# Joakims_fulle_kort_kretsskjema.net
KiCad netlist of a schematic drawn in EasyEDA
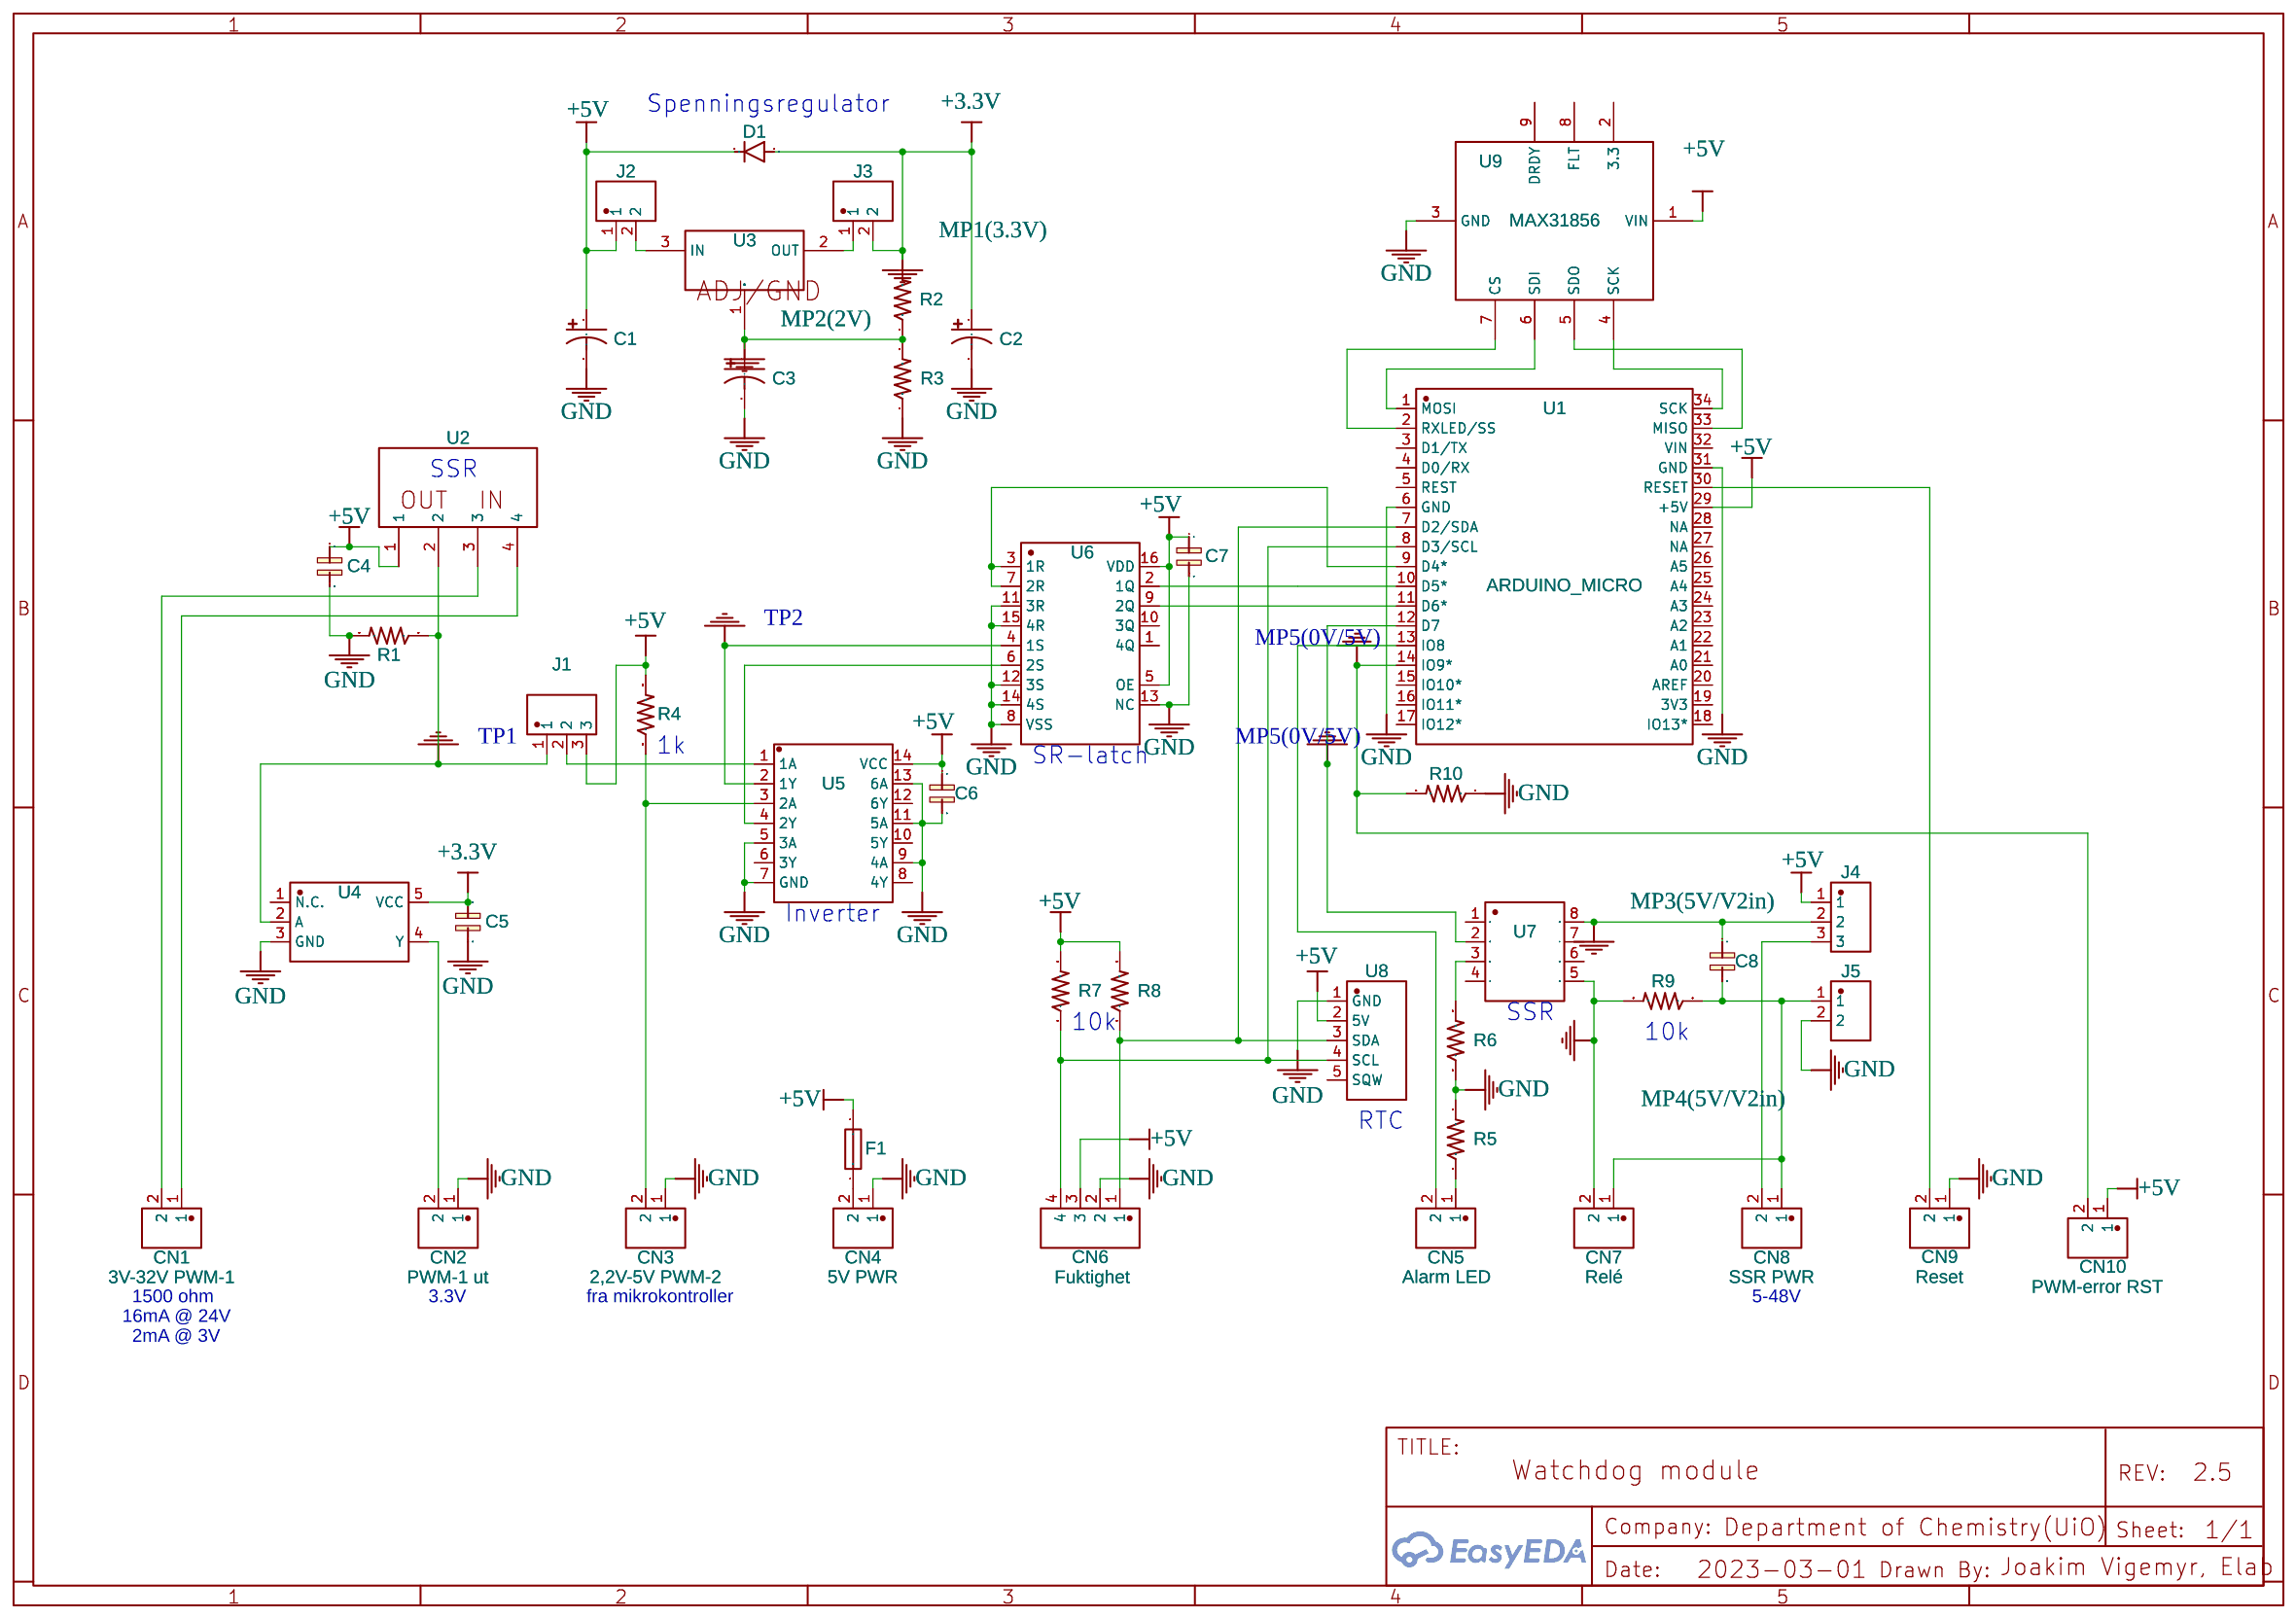
[diagram p0: schematic sheet]

(export (version "E")
  (design (tool "Eeschema 10.0.6"))
  (components
    (comp (ref "C1") (value "10uF") (libsource (lib "") (part "CAP_POLPTH1")))
    (comp (ref "C2") (value "100uF") (libsource (lib "") (part "CAP_POLPTH1")))
    (comp (ref "C3") (value "47uF") (libsource (lib "") (part "CAP_POLPTH1_1")))
    (comp (ref "C4")
      (value "C_3216MP")
      (fields (field (name "BOM_Manufacturer Part") "?"))
      (libsource (lib "") (part "Unknown_-60_-570"))
    )
    (comp (ref "C5")
      (value "C_3216MP")
      (fields (field (name "BOM_Manufacturer Part") "?"))
      (libsource (lib "") (part "Unknown_10_-390"))
    )
    (comp (ref "C6")
      (value "C_3216MP")
      (fields (field (name "BOM_Manufacturer Part") "?"))
      (libsource (lib "") (part "Unknown_250_-455"))
    )
    (comp (ref "C7")
      (value "C_3216MP")
      (fields (field (name "BOM_Manufacturer Part") "?"))
      (libsource (lib "") (part "Unknown_375_-575"))
    )
    (comp (ref "C8")
      (value "C_3216MP")
      (fields (field (name "BOM_Manufacturer Part") "?"))
      (libsource (lib "") (part "Unknown_645_-370"))
    )
    (comp (ref "CN1")
      (value "3V-32V PWM-1")
      (fields (field (name "BOM_Manufacturer Part") "1754436") (field (name "BOM_Supplier Part") "C3586499"))
      (libsource (lib "") (part "1754436"))
    )
    (comp (ref "CN2")
      (value "PWM-1 ut")
      (fields (field (name "BOM_Manufacturer Part") "1754436") (field (name "BOM_Supplier Part") "C3586499"))
      (libsource (lib "") (part "1754436"))
    )
    (comp (ref "CN3")
      (value "2,2V-5V PWM-2")
      (fields (field (name "BOM_Manufacturer Part") "1754436") (field (name "BOM_Supplier Part") "C3586499"))
      (libsource (lib "") (part "1754436"))
    )
    (comp (ref "CN4")
      (value "5V PWR")
      (fields (field (name "BOM_Manufacturer Part") "1754436") (field (name "BOM_Supplier Part") "C3586499"))
      (libsource (lib "") (part "1754436"))
    )
    (comp (ref "CN5")
      (value "Alarm LED")
      (fields (field (name "BOM_Manufacturer Part") "1754436") (field (name "BOM_Supplier Part") "C3586499"))
      (libsource (lib "") (part "1754436"))
    )
    (comp (ref "CN6")
      (value "Fuktighet")
      (fields (field (name "BOM_Manufacturer Part") "1888700") (field (name "BOM_Supplier Part") "C3816378"))
      (libsource (lib "") (part "1888700"))
    )
    (comp (ref "CN7")
      (value "Relé")
      (fields (field (name "BOM_Manufacturer Part") "1754436") (field (name "BOM_Supplier Part") "C3586499"))
      (libsource (lib "") (part "1754436"))
    )
    (comp (ref "CN8")
      (value "SSR PWR")
      (fields (field (name "BOM_Manufacturer Part") "1754436") (field (name "BOM_Supplier Part") "C3586499"))
      (libsource (lib "") (part "1754436"))
    )
    (comp (ref "CN9")
      (value "Reset")
      (fields (field (name "BOM_Manufacturer Part") "1754436") (field (name "BOM_Supplier Part") "C3586499"))
      (libsource (lib "") (part "1754436"))
    )
    (comp (ref "CN10")
      (value "PWM-error RST")
      (fields (field (name "BOM_Manufacturer Part") "1754436") (field (name "BOM_Supplier Part") "C3586499"))
      (libsource (lib "") (part "1754436"))
    )
    (comp (ref "D1") (value "1N4007") (libsource (lib "") (part "DIODEKIT2")))
    (comp (ref "F1")
      (value "0326025.MXP")
      (fields (field (name "BOM_Supplier Part") "C178977"))
      (libsource (lib "") (part "0326025.MXP"))
    )
    (comp (ref "J1")
      (value "JUMPER3")
      (fields (field (name "BOM_Manufacturer Part") "Jumper3") (field (name "BOM_Supplier Part") "C2940050"))
      (libsource (lib "") (part "JUMPER3"))
    )
    (comp (ref "J2")
      (value "JUMPER2")
      (fields (field (name "BOM_Manufacturer Part") "Jumper2") (field (name "BOM_Supplier Part") "C2940092"))
      (libsource (lib "") (part "JUMPER2_1"))
    )
    (comp (ref "J3")
      (value "JUMPER2")
      (fields (field (name "BOM_Manufacturer Part") "Jumper2") (field (name "BOM_Supplier Part") "C2940092"))
      (libsource (lib "") (part "JUMPER2_1"))
    )
    (comp (ref "J4")
      (value "JUMPER3")
      (fields (field (name "BOM_Manufacturer Part") "Jumper3") (field (name "BOM_Supplier Part") "C2940050"))
      (libsource (lib "") (part "JUMPER3_1"))
    )
    (comp (ref "J5")
      (value "JUMPER2")
      (fields (field (name "BOM_Manufacturer Part") "Jumper2") (field (name "BOM_Supplier Part") "C2940092"))
      (libsource (lib "") (part "JUMPER2"))
    )
    (comp (ref "R1") (value "200ohm") (libsource (lib "") (part "RESISTORPTH-14W-VERT_1")))
    (comp (ref "R2") (value "200ohm") (libsource (lib "") (part "RESISTORPTH-14W-VERT")))
    (comp (ref "R3") (value "330ohm") (libsource (lib "") (part "RESISTORPTH-14W-VERT")))
    (comp (ref "R4") (value "1k") (libsource (lib "") (part "RESISTORPTH-14W-VERT")))
    (comp (ref "R5") (value "180ohm") (libsource (lib "") (part "RESISTORPTH-14W-VERT")))
    (comp (ref "R6") (value "330ohm") (libsource (lib "") (part "RESISTORPTH-14W-VERT")))
    (comp (ref "R7") (value "10k") (libsource (lib "") (part "RESISTORPTH-14W-VERT")))
    (comp (ref "R8") (value "10k") (libsource (lib "") (part "RESISTORPTH-14W-VERT")))
    (comp (ref "R9") (value "10k") (libsource (lib "") (part "RESISTORPTH-14W-VERT_1")))
    (comp (ref "R10") (value "10k") (libsource (lib "") (part "RESISTORPTH-14W-VERT_1")))
    (comp (ref "U1") (value "ARDUINO_MICRO") (libsource (lib "") (part "ARDUINO_MICRO")))
    (comp (ref "U2")
      (value "MPDCD3")
      (fields (field (name "BOM_Manufacturer Part") "MPDCD3-B") (field (name "BOM_Supplier Part") "C2616825"))
      (libsource (lib "") (part "MPDCD3-B"))
    )
    (comp (ref "U3")
      (value "TLV1117")
      (fields
        (field (name "BOM_Manufacturer Part") "TLV1117-18CKVURG3")
        (field (name "BOM_Supplier Part") "C2870812")
      )
      (libsource (lib "") (part "TLV1117-18CKVURG3"))
    )
    (comp (ref "U4")
      (value "SN74LVC1G34")
      (fields
        (field (name "BOM_Manufacturer Part") "SN74LVC1G17DBVT")
        (field (name "BOM_Supplier Part") "C2862344")
      )
      (libsource (lib "") (part "SN74LVC1G17DBVT"))
    )
    (comp (ref "U5")
      (value "SN74ACT04D")
      (fields
        (field (name "BOM_Manufacturer Part") "SN74AC04DR")
        (field (name "BOM_Supplier Part") "C352940")
      )
      (libsource (lib "") (part "SN74AC04DR"))
    )
    (comp (ref "U6")
      (value "HEF4043BT,652")
      (fields
        (field (name "BOM_Manufacturer Part") "HEF4543BT,653")
        (field (name "BOM_Supplier Part") "C131489")
      )
      (libsource (lib "") (part "Unknown_320_-570"))
    )
    (comp (ref "U7")
      (value "XR2A-0811-N")
      (fields (field (name "BOM_Supplier Part") "C231487"))
      (libsource (lib "") (part "XR2A-0811-N"))
    )
    (comp (ref "U8") (value "DS1307") (libsource (lib "") (part "DS1307")))
    (comp (ref "U9") (value "MAX31856") (libsource (lib "") (part "Unknown_560_-735")))
  )
  (nets
    (net (code "1") (name "+3.3V") (class "Default")
      (node (ref "C2") (pin "1") (pinfunction "+_1") (pintype "unspecified"))
      (node (ref "C5") (pin "1") (pinfunction "1_1") (pintype "bidirectional"))
      (node (ref "D1") (pin "A") (pinfunction "A_A") (pintype "unspecified"))
      (node (ref "J3") (pin "2") (pinfunction "2_2") (pintype "unspecified"))
      (node (ref "R2") (pin "P$2") (pinfunction "2_P$2") (pintype "unspecified"))
      (node (ref "U4") (pin "5") (pinfunction "VCC_5") (pintype "unspecified"))
    )
    (net (code "2") (name "+5V") (class "Default")
      (node (ref "C1") (pin "1") (pinfunction "+_1") (pintype "unspecified"))
      (node (ref "C4") (pin "1") (pinfunction "1_1") (pintype "bidirectional"))
      (node (ref "C6") (pin "1") (pinfunction "1_1") (pintype "bidirectional"))
      (node (ref "C7") (pin "1") (pinfunction "1_1") (pintype "bidirectional"))
      (node (ref "CN10") (pin "1") (pinfunction "1_1") (pintype "unspecified"))
      (node (ref "CN6") (pin "3") (pinfunction "3_3") (pintype "unspecified"))
      (node (ref "D1") (pin "C") (pinfunction "C_C") (pintype "unspecified"))
      (node (ref "F1") (pin "2") (pinfunction "2_2") (pintype "unspecified"))
      (node (ref "J1") (pin "3") (pinfunction "3_3") (pintype "unspecified"))
      (node (ref "J2") (pin "1") (pinfunction "1_1") (pintype "unspecified"))
      (node (ref "J4") (pin "1") (pinfunction "1_1") (pintype "unspecified"))
      (node (ref "R4") (pin "P$2") (pinfunction "2_P$2") (pintype "unspecified"))
      (node (ref "R7") (pin "P$2") (pinfunction "2_P$2") (pintype "unspecified"))
      (node (ref "R8") (pin "P$2") (pinfunction "2_P$2") (pintype "unspecified"))
      (node (ref "U1") (pin "29") (pinfunction "+5V_29") (pintype "unspecified"))
      (node (ref "U2") (pin "1") (pinfunction "1_1") (pintype "unspecified"))
      (node (ref "U5") (pin "14") (pinfunction "VCC_14") (pintype "unspecified"))
      (node (ref "U6") (pin "16") (pinfunction "VDD_16") (pintype "unspecified"))
      (node (ref "U6") (pin "5") (pinfunction "OE_5") (pintype "unspecified"))
      (node (ref "U8") (pin "2") (pinfunction "5V_2") (pintype "unspecified"))
      (node (ref "U9") (pin "1") (pinfunction "VIN_1") (pintype "unspecified"))
    )
    (net (code "3") (name "GND") (class "Default")
      (node (ref "C1") (pin "2") (pinfunction "-_2") (pintype "unspecified"))
      (node (ref "C2") (pin "2") (pinfunction "-_2") (pintype "unspecified"))
      (node (ref "C3") (pin "2") (pinfunction "-_2") (pintype "unspecified"))
      (node (ref "C4") (pin "2") (pinfunction "2_2") (pintype "bidirectional"))
      (node (ref "C5") (pin "2") (pinfunction "2_2") (pintype "bidirectional"))
      (node (ref "C6") (pin "2") (pinfunction "2_2") (pintype "bidirectional"))
      (node (ref "C7") (pin "2") (pinfunction "2_2") (pintype "bidirectional"))
      (node (ref "CN2") (pin "1") (pinfunction "1_1") (pintype "unspecified"))
      (node (ref "CN3") (pin "1") (pinfunction "1_1") (pintype "unspecified"))
      (node (ref "CN4") (pin "1") (pinfunction "1_1") (pintype "unspecified"))
      (node (ref "CN6") (pin "2") (pinfunction "2_2") (pintype "unspecified"))
      (node (ref "CN9") (pin "1") (pinfunction "1_1") (pintype "unspecified"))
      (node (ref "J5") (pin "2") (pinfunction "2_2") (pintype "unspecified"))
      (node (ref "R1") (pin "P$2") (pinfunction "2_P$2") (pintype "unspecified"))
      (node (ref "R10") (pin "P$1") (pinfunction "1_P$1") (pintype "unspecified"))
      (node (ref "R3") (pin "P$1") (pinfunction "1_P$1") (pintype "unspecified"))
      (node (ref "R5") (pin "P$2") (pinfunction "2_P$2") (pintype "unspecified"))
      (node (ref "R6") (pin "P$1") (pinfunction "1_P$1") (pintype "unspecified"))
      (node (ref "U1") (pin "31") (pinfunction "GND_31") (pintype "unspecified"))
      (node (ref "U1") (pin "6") (pinfunction "GND_6") (pintype "unspecified"))
      (node (ref "U4") (pin "3") (pinfunction "GND_3") (pintype "unspecified"))
      (node (ref "U5") (pin "11") (pinfunction "5A_11") (pintype "unspecified"))
      (node (ref "U5") (pin "13") (pinfunction "6A_13") (pintype "unspecified"))
      (node (ref "U5") (pin "5") (pinfunction "3A_5") (pintype "unspecified"))
      (node (ref "U5") (pin "7") (pinfunction "GND_7") (pintype "unspecified"))
      (node (ref "U5") (pin "9") (pinfunction "4A_9") (pintype "unspecified"))
      (node (ref "U6") (pin "11") (pinfunction "3R_11") (pintype "unspecified"))
      (node (ref "U6") (pin "12") (pinfunction "3S_12") (pintype "unspecified"))
      (node (ref "U6") (pin "13") (pinfunction "NC_13") (pintype "unspecified"))
      (node (ref "U6") (pin "14") (pinfunction "4S_14") (pintype "unspecified"))
      (node (ref "U6") (pin "15") (pinfunction "4R_15") (pintype "unspecified"))
      (node (ref "U6") (pin "8") (pinfunction "VSS_8") (pintype "unspecified"))
      (node (ref "U8") (pin "1") (pinfunction "GND_1") (pintype "unspecified"))
      (node (ref "U9") (pin "3") (pinfunction "GND_3") (pintype "unspecified"))
    )
    (net (code "4") (name "MP2(2V)") (class "Default")
      (node (ref "C3") (pin "1") (pinfunction "+_1") (pintype "unspecified"))
      (node (ref "R2") (pin "P$1") (pinfunction "1_P$1") (pintype "unspecified"))
      (node (ref "R3") (pin "P$2") (pinfunction "2_P$2") (pintype "unspecified"))
      (node (ref "U3") (pin "1") (pinfunction "ADJ/GND_1") (pintype "passive"))
    )
    (net (code "5") (name "MP3(5V{slash}V2in)") (class "Default")
      (node (ref "C8") (pin "1") (pinfunction "1_1") (pintype "bidirectional"))
      (node (ref "J4") (pin "2") (pinfunction "2_2") (pintype "unspecified"))
      (node (ref "U7") (pin "8") (pinfunction "8_8") (pintype "unspecified"))
    )
    (net (code "6") (name "MP4(5V{slash}V2in)") (class "Default")
      (node (ref "CN7") (pin "2") (pinfunction "2_2") (pintype "unspecified"))
      (node (ref "R9") (pin "P$2") (pinfunction "2_P$2") (pintype "unspecified"))
      (node (ref "U7") (pin "5") (pinfunction "5_5") (pintype "unspecified"))
    )
    (net (code "7") (name "MP5(0V{slash}5V)") (class "Default")
      (node (ref "CN10") (pin "2") (pinfunction "2_2") (pintype "unspecified"))
      (node (ref "R10") (pin "P$2") (pinfunction "2_P$2") (pintype "unspecified"))
      (node (ref "U1") (pin "12") (pinfunction "D7_12") (pintype "unspecified"))
      (node (ref "U1") (pin "14") (pinfunction "IO9*_14") (pintype "unspecified"))
      (node (ref "U7") (pin "2") (pinfunction "2_2") (pintype "unspecified"))
    )
    (net (code "8") (name "Net-(CN1-Pad1)") (class "Default")
      (node (ref "CN1") (pin "1") (pinfunction "1_1") (pintype "unspecified"))
      (node (ref "U2") (pin "4") (pinfunction "4_4") (pintype "unspecified"))
    )
    (net (code "9") (name "Net-(CN1-Pad2)") (class "Default")
      (node (ref "CN1") (pin "2") (pinfunction "2_2") (pintype "unspecified"))
      (node (ref "U2") (pin "3") (pinfunction "3_3") (pintype "unspecified"))
    )
    (net (code "10") (name "Net-(CN4-Pad2)") (class "Default")
      (node (ref "CN4") (pin "2") (pinfunction "2_2") (pintype "unspecified"))
      (node (ref "F1") (pin "1") (pinfunction "1_1") (pintype "unspecified"))
    )
    (net (code "11") (name "Net-(CN8-Pad2)") (class "Default")
      (node (ref "CN8") (pin "2") (pinfunction "2_2") (pintype "unspecified"))
      (node (ref "J4") (pin "3") (pinfunction "3_3") (pintype "unspecified"))
    )
    (net (code "12") (name "Net-(R4-1)") (class "Default")
      (node (ref "CN3") (pin "2") (pinfunction "2_2") (pintype "unspecified"))
      (node (ref "R4") (pin "P$1") (pinfunction "1_P$1") (pintype "unspecified"))
      (node (ref "U5") (pin "3") (pinfunction "2A_3") (pintype "unspecified"))
    )
    (net (code "13") (name "Net-(R5-1)") (class "Default")
      (node (ref "CN5") (pin "1") (pinfunction "1_1") (pintype "unspecified"))
      (node (ref "R5") (pin "P$1") (pinfunction "1_P$1") (pintype "unspecified"))
    )
    (net (code "14") (name "Net-(R6-2)") (class "Default")
      (node (ref "R6") (pin "P$2") (pinfunction "2_P$2") (pintype "unspecified"))
      (node (ref "U7") (pin "3") (pinfunction "3_3") (pintype "unspecified"))
    )
    (net (code "15") (name "Net-(R7-1)") (class "Default")
      (node (ref "CN6") (pin "4") (pinfunction "4_4") (pintype "unspecified"))
      (node (ref "R7") (pin "P$1") (pinfunction "1_P$1") (pintype "unspecified"))
      (node (ref "U1") (pin "8") (pinfunction "D3/SCL_8") (pintype "unspecified"))
      (node (ref "U8") (pin "4") (pinfunction "SCL_4") (pintype "unspecified"))
    )
    (net (code "16") (name "Net-(R8-1)") (class "Default")
      (node (ref "CN6") (pin "1") (pinfunction "1_1") (pintype "unspecified"))
      (node (ref "R8") (pin "P$1") (pinfunction "1_P$1") (pintype "unspecified"))
      (node (ref "U1") (pin "7") (pinfunction "D2/SDA_7") (pintype "unspecified"))
      (node (ref "U8") (pin "3") (pinfunction "SDA_3") (pintype "unspecified"))
    )
    (net (code "17") (name "Net-(R9-1)") (class "Default")
      (node (ref "C8") (pin "2") (pinfunction "2_2") (pintype "bidirectional"))
      (node (ref "CN7") (pin "1") (pinfunction "1_1") (pintype "unspecified"))
      (node (ref "CN8") (pin "1") (pinfunction "1_1") (pintype "unspecified"))
      (node (ref "J5") (pin "1") (pinfunction "1_1") (pintype "unspecified"))
      (node (ref "R9") (pin "P$1") (pinfunction "1_P$1") (pintype "unspecified"))
    )
    (net (code "18") (name "Net-(U1-D4*)") (class "Default")
      (node (ref "U1") (pin "9") (pinfunction "D4*_9") (pintype "unspecified"))
      (node (ref "U6") (pin "3") (pinfunction "1R_3") (pintype "unspecified"))
      (node (ref "U6") (pin "7") (pinfunction "2R_7") (pintype "unspecified"))
    )
    (net (code "19") (name "Net-(U1-D5*)") (class "Default")
      (node (ref "U1") (pin "10") (pinfunction "D5*_10") (pintype "unspecified"))
      (node (ref "U6") (pin "2") (pinfunction "1Q_2") (pintype "unspecified"))
    )
    (net (code "20") (name "Net-(U1-D6*)") (class "Default")
      (node (ref "U1") (pin "11") (pinfunction "D6*_11") (pintype "unspecified"))
      (node (ref "U6") (pin "9") (pinfunction "2Q_9") (pintype "unspecified"))
    )
    (net (code "21") (name "Net-(U1-IO8)") (class "Default")
      (node (ref "CN5") (pin "2") (pinfunction "2_2") (pintype "unspecified"))
      (node (ref "U1") (pin "13") (pinfunction "IO8_13") (pintype "unspecified"))
    )
    (net (code "22") (name "Net-(U1-MISO)") (class "Default")
      (node (ref "U1") (pin "33") (pinfunction "MISO_33") (pintype "unspecified"))
      (node (ref "U9") (pin "5") (pinfunction "SDO_5") (pintype "unspecified"))
    )
    (net (code "23") (name "Net-(U1-MOSI)") (class "Default")
      (node (ref "U1") (pin "1") (pinfunction "MOSI_1") (pintype "unspecified"))
      (node (ref "U9") (pin "6") (pinfunction "SDI_6") (pintype "unspecified"))
    )
    (net (code "24") (name "Net-(U1-RESET)") (class "Default")
      (node (ref "CN9") (pin "2") (pinfunction "2_2") (pintype "unspecified"))
      (node (ref "U1") (pin "30") (pinfunction "RESET_30") (pintype "unspecified"))
    )
    (net (code "25") (name "Net-(U1-RXLED{slash}SS)") (class "Default")
      (node (ref "U1") (pin "2") (pinfunction "RXLED/SS_2") (pintype "unspecified"))
      (node (ref "U9") (pin "7") (pinfunction "CS_7") (pintype "unspecified"))
    )
    (net (code "26") (name "Net-(U1-SCK)") (class "Default")
      (node (ref "U1") (pin "34") (pinfunction "SCK_34") (pintype "unspecified"))
      (node (ref "U9") (pin "4") (pinfunction "SCK_4") (pintype "unspecified"))
    )
    (net (code "27") (name "Net-(U3-IN)") (class "Default")
      (node (ref "J2") (pin "2") (pinfunction "2_2") (pintype "unspecified"))
      (node (ref "U3") (pin "3") (pinfunction "IN_3") (pintype "passive"))
    )
    (net (code "28") (name "Net-(U3-OUT)") (class "Default")
      (node (ref "J3") (pin "1") (pinfunction "1_1") (pintype "unspecified"))
      (node (ref "U3") (pin "2") (pinfunction "OUT_2") (pintype "passive"))
    )
    (net (code "29") (name "Net-(U4-Y)") (class "Default")
      (node (ref "CN2") (pin "2") (pinfunction "2_2") (pintype "unspecified"))
      (node (ref "U4") (pin "4") (pinfunction "Y_4") (pintype "unspecified"))
    )
    (net (code "30") (name "Net-(U5-1A)") (class "Default")
      (node (ref "J1") (pin "2") (pinfunction "2_2") (pintype "unspecified"))
      (node (ref "U5") (pin "1") (pinfunction "1A_1") (pintype "unspecified"))
    )
    (net (code "31") (name "Net-(U5-2Y)") (class "Default")
      (node (ref "U5") (pin "4") (pinfunction "2Y_4") (pintype "unspecified"))
      (node (ref "U6") (pin "6") (pinfunction "2S_6") (pintype "unspecified"))
    )
    (net (code "32") (name "TP1") (class "Default")
      (node (ref "J1") (pin "1") (pinfunction "1_1") (pintype "unspecified"))
      (node (ref "R1") (pin "P$1") (pinfunction "1_P$1") (pintype "unspecified"))
      (node (ref "U2") (pin "2") (pinfunction "2_2") (pintype "unspecified"))
      (node (ref "U4") (pin "2") (pinfunction "A_2") (pintype "unspecified"))
    )
    (net (code "33") (name "TP2") (class "Default")
      (node (ref "U5") (pin "2") (pinfunction "1Y_2") (pintype "unspecified"))
      (node (ref "U6") (pin "4") (pinfunction "1S_4") (pintype "unspecified"))
    )
    (net (code "34") (name "unconnected-(U1-3V3-Pad19)") (class "Default")
      (node (ref "U1") (pin "19") (pinfunction "3V3_19") (pintype "unspecified"))
    )
    (net (code "35") (name "unconnected-(U1-A0-Pad21)") (class "Default")
      (node (ref "U1") (pin "21") (pinfunction "A0_21") (pintype "unspecified"))
    )
    (net (code "36") (name "unconnected-(U1-A1-Pad22)") (class "Default")
      (node (ref "U1") (pin "22") (pinfunction "A1_22") (pintype "unspecified"))
    )
    (net (code "37") (name "unconnected-(U1-A2-Pad23)") (class "Default")
      (node (ref "U1") (pin "23") (pinfunction "A2_23") (pintype "unspecified"))
    )
    (net (code "38") (name "unconnected-(U1-A3-Pad24)") (class "Default")
      (node (ref "U1") (pin "24") (pinfunction "A3_24") (pintype "unspecified"))
    )
    (net (code "39") (name "unconnected-(U1-A4-Pad25)") (class "Default")
      (node (ref "U1") (pin "25") (pinfunction "A4_25") (pintype "unspecified"))
    )
    (net (code "40") (name "unconnected-(U1-A5-Pad26)") (class "Default")
      (node (ref "U1") (pin "26") (pinfunction "A5_26") (pintype "unspecified"))
    )
    (net (code "41") (name "unconnected-(U1-AREF-Pad20)") (class "Default")
      (node (ref "U1") (pin "20") (pinfunction "AREF_20") (pintype "unspecified"))
    )
    (net (code "42") (name "unconnected-(U1-D0{slash}RX-Pad4)") (class "Default")
      (node (ref "U1") (pin "4") (pinfunction "D0/RX_4") (pintype "unspecified"))
    )
    (net (code "43") (name "unconnected-(U1-D1{slash}TX-Pad3)") (class "Default")
      (node (ref "U1") (pin "3") (pinfunction "D1/TX_3") (pintype "unspecified"))
    )
    (net (code "44") (name "unconnected-(U1-IO10*-Pad15)") (class "Default")
      (node (ref "U1") (pin "15") (pinfunction "IO10*_15") (pintype "unspecified"))
    )
    (net (code "45") (name "unconnected-(U1-IO11*-Pad16)") (class "Default")
      (node (ref "U1") (pin "16") (pinfunction "IO11*_16") (pintype "unspecified"))
    )
    (net (code "46") (name "unconnected-(U1-IO12*-Pad17)") (class "Default")
      (node (ref "U1") (pin "17") (pinfunction "IO12*_17") (pintype "unspecified"))
    )
    (net (code "47") (name "unconnected-(U1-IO13*-Pad18)") (class "Default")
      (node (ref "U1") (pin "18") (pinfunction "IO13*_18") (pintype "unspecified"))
    )
    (net (code "48") (name "unconnected-(U1-NA-Pad27)") (class "Default")
      (node (ref "U1") (pin "27") (pinfunction "NA_27") (pintype "unspecified"))
    )
    (net (code "49") (name "unconnected-(U1-NA-Pad28)") (class "Default")
      (node (ref "U1") (pin "28") (pinfunction "NA_28") (pintype "unspecified"))
    )
    (net (code "50") (name "unconnected-(U1-REST-Pad5)") (class "Default")
      (node (ref "U1") (pin "5") (pinfunction "REST_5") (pintype "unspecified"))
    )
    (net (code "51") (name "unconnected-(U1-VIN-Pad32)") (class "Default")
      (node (ref "U1") (pin "32") (pinfunction "VIN_32") (pintype "unspecified"))
    )
    (net (code "52") (name "unconnected-(U4-N.C.-Pad1)") (class "Default")
      (node (ref "U4") (pin "1") (pinfunction "N.C._1") (pintype "unspecified"))
    )
    (net (code "53") (name "unconnected-(U5-3Y-Pad6)") (class "Default")
      (node (ref "U5") (pin "6") (pinfunction "3Y_6") (pintype "unspecified"))
    )
    (net (code "54") (name "unconnected-(U5-4Y-Pad8)") (class "Default")
      (node (ref "U5") (pin "8") (pinfunction "4Y_8") (pintype "unspecified"))
    )
    (net (code "55") (name "unconnected-(U5-5Y-Pad10)") (class "Default")
      (node (ref "U5") (pin "10") (pinfunction "5Y_10") (pintype "unspecified"))
    )
    (net (code "56") (name "unconnected-(U5-6Y-Pad12)") (class "Default")
      (node (ref "U5") (pin "12") (pinfunction "6Y_12") (pintype "unspecified"))
    )
    (net (code "57") (name "unconnected-(U6-3Q-Pad10)") (class "Default")
      (node (ref "U6") (pin "10") (pinfunction "3Q_10") (pintype "unspecified"))
    )
    (net (code "58") (name "unconnected-(U6-4Q-Pad1)") (class "Default")
      (node (ref "U6") (pin "1") (pinfunction "4Q_1") (pintype "unspecified"))
    )
    (net (code "59") (name "unconnected-(U7-Pad1)") (class "Default")
      (node (ref "U7") (pin "1") (pinfunction "1_1") (pintype "unspecified"))
    )
    (net (code "60") (name "unconnected-(U7-Pad4)") (class "Default")
      (node (ref "U7") (pin "4") (pinfunction "4_4") (pintype "unspecified"))
    )
    (net (code "61") (name "unconnected-(U7-Pad6)") (class "Default")
      (node (ref "U7") (pin "6") (pinfunction "6_6") (pintype "unspecified"))
    )
    (net (code "62") (name "unconnected-(U7-Pad7)") (class "Default")
      (node (ref "U7") (pin "7") (pinfunction "7_7") (pintype "unspecified"))
    )
    (net (code "63") (name "unconnected-(U8-SQW-Pad5)") (class "Default")
      (node (ref "U8") (pin "5") (pinfunction "SQW_5") (pintype "unspecified"))
    )
    (net (code "64") (name "unconnected-(U9-3.3-Pad2)") (class "Default")
      (node (ref "U9") (pin "2") (pinfunction "3.3_2") (pintype "unspecified"))
    )
    (net (code "65") (name "unconnected-(U9-DRDY-Pad9)") (class "Default")
      (node (ref "U9") (pin "9") (pinfunction "DRDY_9") (pintype "unspecified"))
    )
    (net (code "66") (name "unconnected-(U9-FLT-Pad8)") (class "Default")
      (node (ref "U9") (pin "8") (pinfunction "FLT_8") (pintype "unspecified"))
    )
  )
)
